# HDMI.net
KiCad netlist of a schematic drawn in Altium Designer
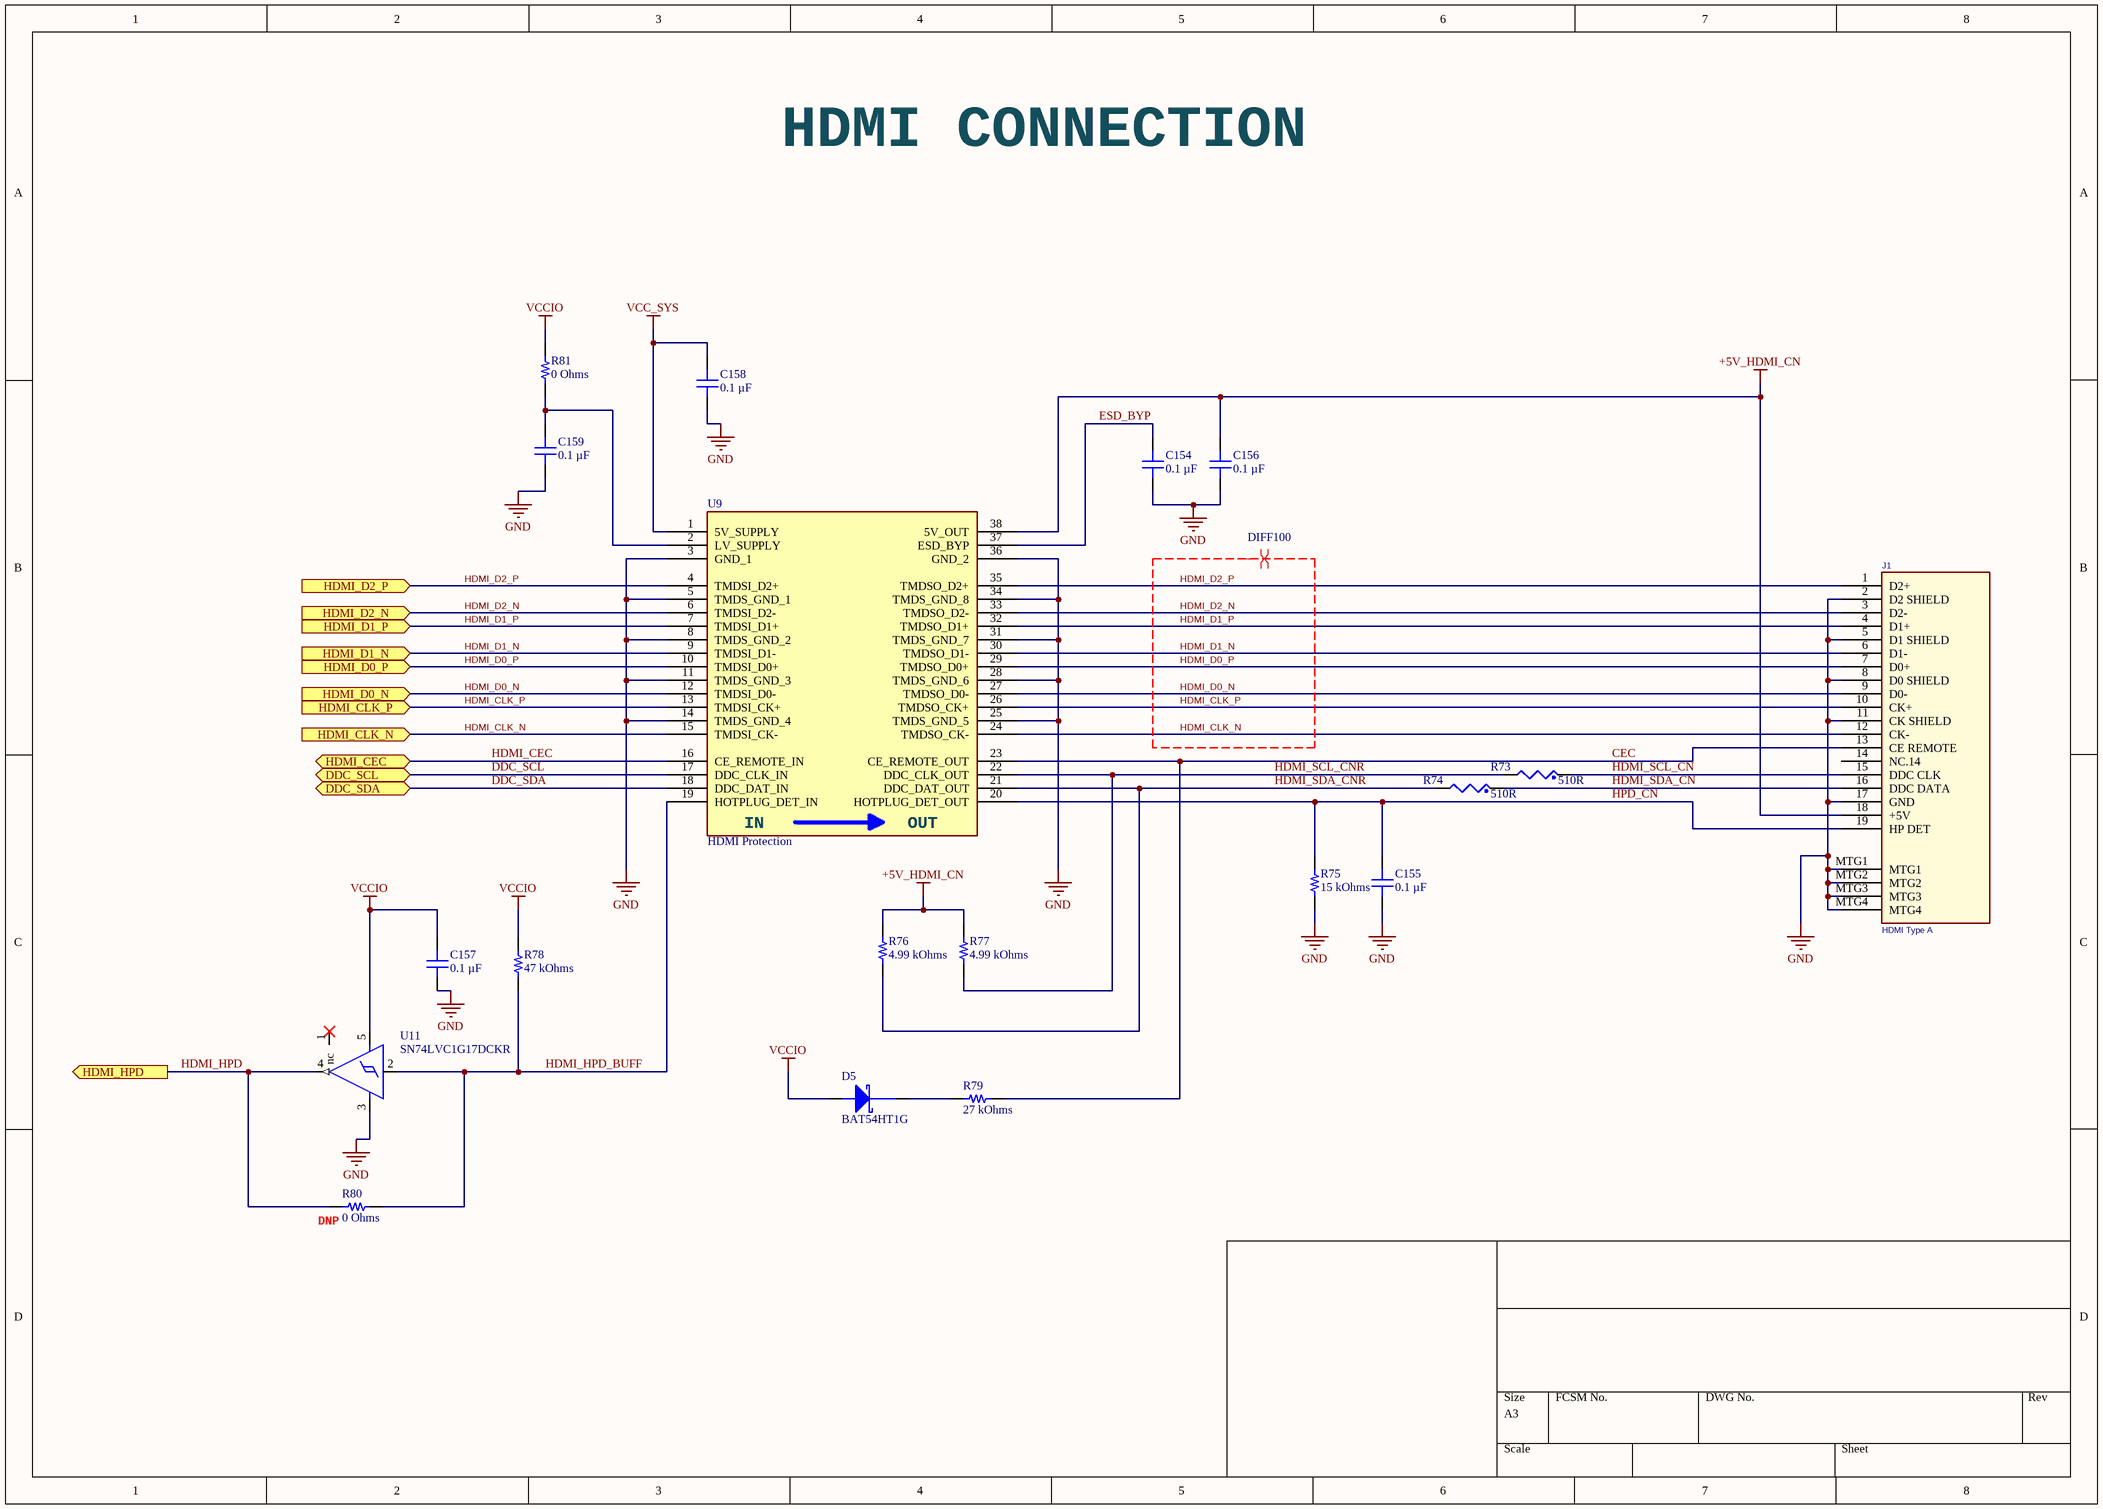
[diagram p0: HDMI.SchDoc]

(export (version "E")
  (design (tool "Eeschema 10.0.6"))
  (components
    (comp (ref "C154")
      (value "0.1 µF")
      (footprint "CAP 0402_1005")
      (description "CAP CER 0.1UF 10V Y5V 0402")
      (fields (field (name "PART NUMBER") "CC0402ZRY5V6BB104") (field (name "MANUFACTURER") "Yageo"))
      (libsource (lib "Celestial Altium Library - altium_library") (part "Capacitor"))
    )
    (comp (ref "C155")
      (value "0.1 µF")
      (footprint "CAP 0402_1005")
      (description "CAP CER 0.1UF 10V Y5V 0402")
      (fields (field (name "PART NUMBER") "CC0402ZRY5V6BB104") (field (name "MANUFACTURER") "Yageo"))
      (libsource (lib "Celestial Altium Library - altium_library") (part "Capacitor"))
    )
    (comp (ref "C156")
      (value "0.1 µF")
      (footprint "CAP 0402_1005")
      (description "CAP CER 0.1UF 10V Y5V 0402")
      (fields (field (name "PART NUMBER") "CC0402ZRY5V6BB104") (field (name "MANUFACTURER") "Yageo"))
      (libsource (lib "Celestial Altium Library - altium_library") (part "Capacitor"))
    )
    (comp (ref "C157")
      (value "0.1 µF")
      (footprint "CAP 0402_1005")
      (description "CAP CER 0.1UF 10V Y5V 0402")
      (fields (field (name "PART NUMBER") "CC0402ZRY5V6BB104") (field (name "MANUFACTURER") "Yageo"))
      (libsource (lib "Celestial Altium Library - altium_library") (part "Capacitor"))
    )
    (comp (ref "C158")
      (value "0.1 µF")
      (footprint "CAP 0402_1005")
      (description "CAP CER 0.1UF 10V Y5V 0402")
      (fields (field (name "PART NUMBER") "CC0402ZRY5V6BB104") (field (name "MANUFACTURER") "Yageo"))
      (libsource (lib "Celestial Altium Library - altium_library") (part "Capacitor"))
    )
    (comp (ref "C159")
      (value "0.1 µF")
      (footprint "CAP 0402_1005")
      (description "CAP CER 0.1UF 10V Y5V 0402")
      (fields (field (name "PART NUMBER") "CC0402ZRY5V6BB104") (field (name "MANUFACTURER") "Yageo"))
      (libsource (lib "Celestial Altium Library - altium_library") (part "Capacitor"))
    )
    (comp (ref "D5")
      (value "BAT54HT1G")
      (footprint "SOD323")
      (description "DIODE SCHOTTKY 30V 0.2A SOD323")
      (fields (field (name "MANUFACTURER") "Fairchild Semiconductor"))
      (libsource (lib "AAR_RockChip_RK3328") (part "BAT54HT1G"))
    )
    (comp (ref "J1")
      (value "HDMI Type A")
      (footprint "HDMI Type-A")
      (description "CONN RCPT 19POS HDMI RT ANG SMD")
      (fields
        (field (name "MANUFACTURER") "Molex Connector Corporation")
        (field (name "MANUFACTURER PART NUMBER") "47151-0001")
        (field (name ".CHECKED PCB") "MM")
        (field (name ".CHECKED SCH") "MM")
      )
      (libsource (lib "AAR_RockChip_RK3328") (part "HDMI Type A"))
    )
    (comp (ref "R73")
      (value "510R")
      (footprint "0402_CR")
      (libsource (lib "AAR_RockChip_RK3328") (part "RES"))
    )
    (comp (ref "R74")
      (value "510R")
      (footprint "0402_CR")
      (libsource (lib "AAR_RockChip_RK3328") (part "RES"))
    )
    (comp (ref "R75")
      (value "15 kOhms")
      (footprint "RES 0402_1005")
      (description "RES 15K OHM 1% 1/16W 0402")
      (fields
        (field (name "PART NUMBER") "RMCF0402FT15K0")
        (field (name "MANUFACTURER") "Stackpole Electronics Inc")
      )
      (libsource (lib "Celestial Altium Library - altium_library") (part "Resistor"))
    )
    (comp (ref "R76")
      (value "4.99 kOhms")
      (footprint "RES 0402_1005")
      (description "RES SMD 4.99KOHM 0.1% 1/16W 0402")
      (fields
        (field (name "PART NUMBER") "RN73C1E4K99BTD")
        (field (name "MANUFACTURER") "TE Connectivity Passive Product")
      )
      (libsource (lib "Celestial Altium Library - altium_library") (part "Resistor"))
    )
    (comp (ref "R77")
      (value "4.99 kOhms")
      (footprint "RES 0402_1005")
      (description "RES SMD 4.99KOHM 0.1% 1/16W 0402")
      (fields
        (field (name "PART NUMBER") "RN73C1E4K99BTD")
        (field (name "MANUFACTURER") "TE Connectivity Passive Product")
      )
      (libsource (lib "Celestial Altium Library - altium_library") (part "Resistor"))
    )
    (comp (ref "R78")
      (value "47 kOhms")
      (footprint "RES 0402_1005")
      (description "RES SMD 47K OHM 5% 1/16W 0402")
      (fields (field (name "PART NUMBER") "AC0402JR-0747KL") (field (name "MANUFACTURER") "Yageo"))
      (libsource (lib "Celestial Altium Library - altium_library") (part "Resistor"))
    )
    (comp (ref "R79")
      (value "27 kOhms")
      (footprint "RES 0402_1005")
      (description "RES 27K OHM 5% 1/16W 0402")
      (fields (field (name "PART NUMBER") "RC0402JR-0727KL") (field (name "MANUFACTURER") "Yageo"))
      (libsource (lib "Celestial Altium Library - altium_library") (part "Resistor"))
    )
    (comp (ref "R80")
      (value "0 Ohms")
      (footprint "RES 0402_1005")
      (description "RESA-AS 0402 0R JUMPER 63MW")
      (fields (field (name "PART NUMBER") "CR0402AJ/-000GAS") (field (name "MANUFACTURER") "Bourns Inc."))
      (libsource (lib "Celestial Altium Library - altium_library") (part "Resistor"))
    )
    (comp (ref "R81")
      (value "0 Ohms")
      (footprint "RES 0402_1005")
      (description "RESA-AS 0402 0R JUMPER 63MW")
      (fields (field (name "PART NUMBER") "CR0402AJ/-000GAS") (field (name "MANUFACTURER") "Bourns Inc."))
      (libsource (lib "Celestial Altium Library - altium_library") (part "Resistor"))
    )
    (comp (ref "U9")
      (value "HDMI Protection")
      (footprint "TSSOP50P640X120-38N")
      (description "HDMI Transmitter Port\r\nProtection and Interface\r\nDevice 38-TSSOP")
      (fields
        (field (name "MFR") "ON Semiconductor")
        (field (name "MFR_PART_NO") "CM2020-00TR")
        (field (name "CREATOR") "Arman_Arvand")
      )
      (libsource (lib "AAR_RockChip_RK3328") (part "CM2020-00TR"))
    )
    (comp (ref "U11")
      (value "SN74LVC1G17DCKR")
      (footprint "SC70_5")
      (description "IC BUFFER SCHMIT TRIG SC705")
      (fields
        (field (name "MANUFACTURER") "Texas Instruments")
        (field (name ".CHECKED PCB") "RF")
        (field (name ".CHECKED SCH") "RF")
      )
      (libsource (lib "AAR_RockChip_RK3328") (part "SN74LVC1G17DCKR"))
    )
  )
  (nets
    (net (code "1") (name "+5V_HDMI_CN") (class "Default")
      (node (ref "C156") (pin "2") (pinfunction "2_2") (pintype "passive"))
      (node (ref "J1") (pin "18") (pinfunction "+5V_18") (pintype "passive"))
      (node (ref "R76") (pin "2") (pinfunction "2_2") (pintype "passive"))
      (node (ref "R77") (pin "2") (pinfunction "2_2") (pintype "passive"))
      (node (ref "U9") (pin "38") (pinfunction "5V_OUT_38") (pintype "passive"))
    )
    (net (code "2") (name "/CEC") (class "Default")
      (node (ref "J1") (pin "13") (pinfunction "CE_REMOTE_13") (pintype "passive"))
      (node (ref "R79") (pin "2") (pinfunction "2_2") (pintype "passive"))
      (node (ref "U9") (pin "23") (pinfunction "CE_REMOTE_OUT_23") (pintype "passive"))
    )
    (net (code "3") (name "/DDC_SCL") (class "Default")
      (node (ref "U9") (pin "17") (pinfunction "DDC_CLK_IN_17") (pintype "passive"))
    )
    (net (code "4") (name "/DDC_SDA") (class "Default")
      (node (ref "U9") (pin "18") (pinfunction "DDC_DAT_IN_18") (pintype "passive"))
    )
    (net (code "5") (name "/ESD_BYP") (class "Default")
      (node (ref "C154") (pin "2") (pinfunction "2_2") (pintype "passive"))
      (node (ref "U9") (pin "37") (pinfunction "ESD_BYP_37") (pintype "passive"))
    )
    (net (code "6") (name "/HDMI_CEC") (class "Default")
      (node (ref "U9") (pin "16") (pinfunction "CE_REMOTE_IN_16") (pintype "passive"))
    )
    (net (code "7") (name "/HDMI_CLK_N") (class "Default")
      (node (ref "J1") (pin "12") (pinfunction "CK-_12") (pintype "passive"))
      (node (ref "U9") (pin "15") (pinfunction "TMDSI_CK-_15") (pintype "passive"))
      (node (ref "U9") (pin "24") (pinfunction "TMDSO_CK-_24") (pintype "passive"))
    )
    (net (code "8") (name "/HDMI_CLK_P") (class "Default")
      (node (ref "J1") (pin "10") (pinfunction "CK+_10") (pintype "passive"))
      (node (ref "U9") (pin "13") (pinfunction "TMDSI_CK+_13") (pintype "passive"))
      (node (ref "U9") (pin "26") (pinfunction "TMDSO_CK+_26") (pintype "passive"))
    )
    (net (code "9") (name "/HDMI_D0_N") (class "Default")
      (node (ref "J1") (pin "9") (pinfunction "D0-_9") (pintype "passive"))
      (node (ref "U9") (pin "12") (pinfunction "TMDSI_D0-_12") (pintype "passive"))
      (node (ref "U9") (pin "27") (pinfunction "TMDSO_D0-_27") (pintype "passive"))
    )
    (net (code "10") (name "/HDMI_D0_P") (class "Default")
      (node (ref "J1") (pin "7") (pinfunction "D0+_7") (pintype "passive"))
      (node (ref "U9") (pin "10") (pinfunction "TMDSI_D0+_10") (pintype "passive"))
      (node (ref "U9") (pin "29") (pinfunction "TMDSO_D0+_29") (pintype "passive"))
    )
    (net (code "11") (name "/HDMI_D1_N") (class "Default")
      (node (ref "J1") (pin "6") (pinfunction "D1-_6") (pintype "passive"))
      (node (ref "U9") (pin "30") (pinfunction "TMDSO_D1-_30") (pintype "passive"))
      (node (ref "U9") (pin "9") (pinfunction "TMDSI_D1-_9") (pintype "passive"))
    )
    (net (code "12") (name "/HDMI_D1_P") (class "Default")
      (node (ref "J1") (pin "4") (pinfunction "D1+_4") (pintype "passive"))
      (node (ref "U9") (pin "32") (pinfunction "TMDSO_D1+_32") (pintype "passive"))
      (node (ref "U9") (pin "7") (pinfunction "TMDSI_D1+_7") (pintype "passive"))
    )
    (net (code "13") (name "/HDMI_D2_N") (class "Default")
      (node (ref "J1") (pin "3") (pinfunction "D2-_3") (pintype "passive"))
      (node (ref "U9") (pin "33") (pinfunction "TMDSO_D2-_33") (pintype "passive"))
      (node (ref "U9") (pin "6") (pinfunction "TMDSI_D2-_6") (pintype "passive"))
    )
    (net (code "14") (name "/HDMI_D2_P") (class "Default")
      (node (ref "J1") (pin "1") (pinfunction "D2+_1") (pintype "passive"))
      (node (ref "U9") (pin "35") (pinfunction "TMDSO_D2+_35") (pintype "passive"))
      (node (ref "U9") (pin "4") (pinfunction "TMDSI_D2+_4") (pintype "passive"))
    )
    (net (code "15") (name "/HDMI_HPD") (class "Default")
      (node (ref "R80") (pin "1") (pinfunction "1_1") (pintype "passive"))
      (node (ref "U11") (pin "4") (pinfunction "O_4") (pintype "output"))
    )
    (net (code "16") (name "/HDMI_HPD_BUFF") (class "Default")
      (node (ref "R78") (pin "1") (pinfunction "1_1") (pintype "passive"))
      (node (ref "R80") (pin "2") (pinfunction "2_2") (pintype "passive"))
      (node (ref "U11") (pin "2") (pinfunction "I_2") (pintype "passive"))
      (node (ref "U9") (pin "19") (pinfunction "HOTPLUG_DET_IN_19") (pintype "passive"))
    )
    (net (code "17") (name "/HDMI_SCL_CN") (class "Default")
      (node (ref "J1") (pin "15") (pinfunction "DDC_CLK_15") (pintype "passive"))
      (node (ref "R73") (pin "1") (pinfunction "1_1") (pintype "passive"))
    )
    (net (code "18") (name "/HDMI_SCL_CNR") (class "Default")
      (node (ref "R73") (pin "2") (pinfunction "2_2") (pintype "passive"))
      (node (ref "R77") (pin "1") (pinfunction "1_1") (pintype "passive"))
      (node (ref "U9") (pin "22") (pinfunction "DDC_CLK_OUT_22") (pintype "passive"))
    )
    (net (code "19") (name "/HDMI_SDA_CN") (class "Default")
      (node (ref "J1") (pin "16") (pinfunction "DDC_DATA_16") (pintype "passive"))
      (node (ref "R74") (pin "1") (pinfunction "1_1") (pintype "passive"))
    )
    (net (code "20") (name "/HDMI_SDA_CNR") (class "Default")
      (node (ref "R74") (pin "2") (pinfunction "2_2") (pintype "passive"))
      (node (ref "R76") (pin "1") (pinfunction "1_1") (pintype "passive"))
      (node (ref "U9") (pin "21") (pinfunction "DDC_DAT_OUT_21") (pintype "passive"))
    )
    (net (code "21") (name "/HPD_CN") (class "Default")
      (node (ref "C155") (pin "2") (pinfunction "2_2") (pintype "passive"))
      (node (ref "J1") (pin "19") (pinfunction "HP_DET_19") (pintype "passive"))
      (node (ref "R75") (pin "2") (pinfunction "2_2") (pintype "passive"))
      (node (ref "U9") (pin "20") (pinfunction "HOTPLUG_DET_OUT_20") (pintype "passive"))
    )
    (net (code "22") (name "GND") (class "Default")
      (node (ref "C154") (pin "1") (pinfunction "1_1") (pintype "passive"))
      (node (ref "C155") (pin "1") (pinfunction "1_1") (pintype "passive"))
      (node (ref "C156") (pin "1") (pinfunction "1_1") (pintype "passive"))
      (node (ref "C157") (pin "1") (pinfunction "1_1") (pintype "passive"))
      (node (ref "C158") (pin "1") (pinfunction "1_1") (pintype "passive"))
      (node (ref "C159") (pin "1") (pinfunction "1_1") (pintype "passive"))
      (node (ref "J1") (pin "11") (pinfunction "CK_SHIELD_11") (pintype "passive"))
      (node (ref "J1") (pin "17") (pinfunction "GND_17") (pintype "passive"))
      (node (ref "J1") (pin "2") (pinfunction "D2_SHIELD_2") (pintype "passive"))
      (node (ref "J1") (pin "5") (pinfunction "D1_SHIELD_5") (pintype "passive"))
      (node (ref "J1") (pin "8") (pinfunction "D0_SHIELD_8") (pintype "passive"))
      (node (ref "J1") (pin "MTG1") (pinfunction "MTG1_MTG1") (pintype "passive"))
      (node (ref "J1") (pin "MTG2") (pinfunction "MTG2_MTG2") (pintype "passive"))
      (node (ref "J1") (pin "MTG3") (pinfunction "MTG3_MTG3") (pintype "passive"))
      (node (ref "J1") (pin "MTG4") (pinfunction "MTG4_MTG4") (pintype "passive"))
      (node (ref "R75") (pin "1") (pinfunction "1_1") (pintype "passive"))
      (node (ref "U11") (pin "3") (pinfunction "GND_3") (pintype "passive"))
      (node (ref "U9") (pin "11") (pinfunction "TMDS_GND_3_11") (pintype "passive"))
      (node (ref "U9") (pin "14") (pinfunction "TMDS_GND_4_14") (pintype "passive"))
      (node (ref "U9") (pin "25") (pinfunction "TMDS_GND_5_25") (pintype "passive"))
      (node (ref "U9") (pin "28") (pinfunction "TMDS_GND_6_28") (pintype "passive"))
      (node (ref "U9") (pin "3") (pinfunction "GND_1_3") (pintype "passive"))
      (node (ref "U9") (pin "31") (pinfunction "TMDS_GND_7_31") (pintype "passive"))
      (node (ref "U9") (pin "34") (pinfunction "TMDS_GND_8_34") (pintype "passive"))
      (node (ref "U9") (pin "36") (pinfunction "GND_2_36") (pintype "passive"))
      (node (ref "U9") (pin "5") (pinfunction "TMDS_GND_1_5") (pintype "passive"))
      (node (ref "U9") (pin "8") (pinfunction "TMDS_GND_2_8") (pintype "passive"))
    )
    (net (code "23") (name "Net-(D5-Cathode)") (class "Default")
      (node (ref "D5") (pin "1") (pinfunction "Cathode_1") (pintype "passive"))
      (node (ref "R79") (pin "1") (pinfunction "1_1") (pintype "passive"))
    )
    (net (code "24") (name "Net-(U9-LV_SUPPLY)") (class "Default")
      (node (ref "C159") (pin "2") (pinfunction "2_2") (pintype "passive"))
      (node (ref "R81") (pin "1") (pinfunction "1_1") (pintype "passive"))
      (node (ref "U9") (pin "2") (pinfunction "LV_SUPPLY_2") (pintype "passive"))
    )
    (net (code "25") (name "VCCIO") (class "Default")
      (node (ref "C157") (pin "2") (pinfunction "2_2") (pintype "passive"))
      (node (ref "D5") (pin "2") (pinfunction "Anode_2") (pintype "passive"))
      (node (ref "R78") (pin "2") (pinfunction "2_2") (pintype "passive"))
      (node (ref "R81") (pin "2") (pinfunction "2_2") (pintype "passive"))
      (node (ref "U11") (pin "5") (pinfunction "NC1_5") (pintype "passive"))
    )
    (net (code "26") (name "VCC_SYS") (class "Default")
      (node (ref "C158") (pin "2") (pinfunction "2_2") (pintype "passive"))
      (node (ref "U9") (pin "1") (pinfunction "5V_SUPPLY_1") (pintype "passive"))
    )
    (net (code "27") (name "unconnected-(J1-NC.14-Pad14)") (class "Default")
      (node (ref "J1") (pin "14") (pinfunction "NC.14_14") (pintype "passive"))
    )
    (net (code "28") (name "unconnected-(U11-nc-Pad1)") (class "Default")
      (node (ref "U11") (pin "1") (pinfunction "nc_1") (pintype "passive+no_connect"))
    )
  )
)
